# PIC32_Circuit.net
KiCad netlist of a schematic drawn in EAGLE
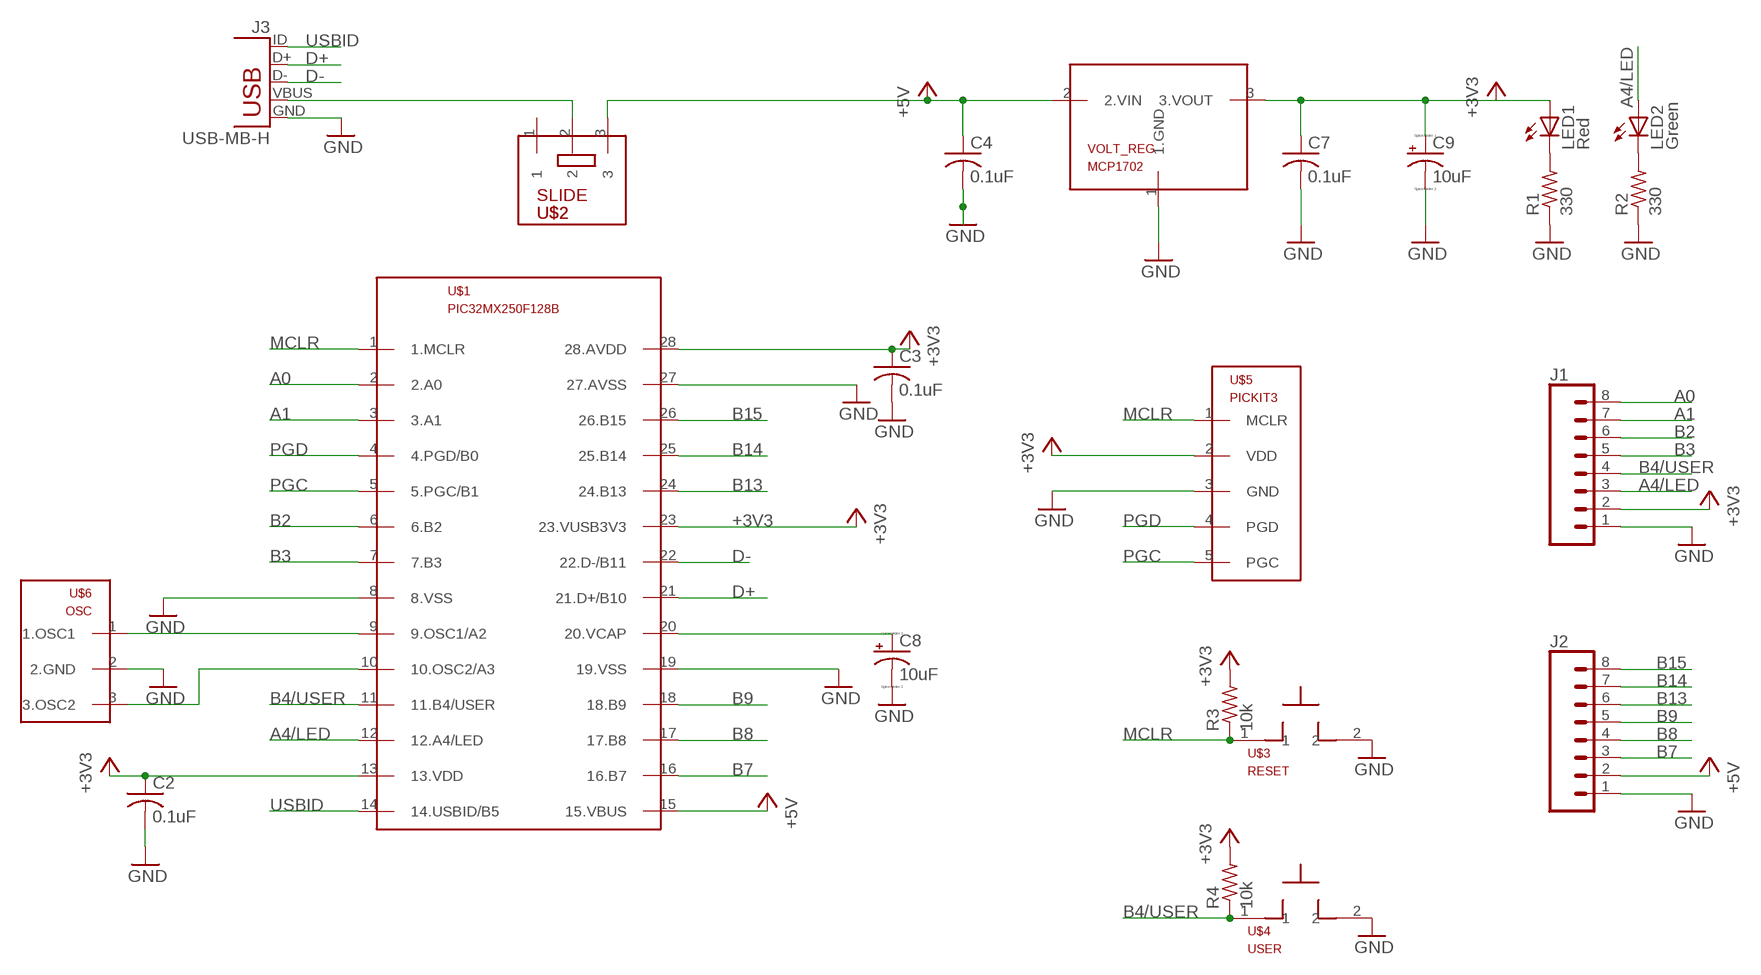
[diagram p0: schematic, sheet 1]

(export (version "E")
  (design (tool "Eeschema 10.0.6"))
  (components
    (comp (ref "C2")
      (value "0.1uF")
      (footprint "eagle-import:C025-050X050")
      (libsource (lib "eagle-import") (part "C-US025-050X050"))
    )
    (comp (ref "C3")
      (value "0.1uF")
      (footprint "eagle-import:C025-050X050")
      (libsource (lib "eagle-import") (part "C-US025-050X050"))
    )
    (comp (ref "C4")
      (value "0.1uF")
      (footprint "eagle-import:C025-050X050")
      (libsource (lib "eagle-import") (part "C-US025-050X050"))
    )
    (comp (ref "C7")
      (value "0.1uF")
      (footprint "eagle-import:C025-050X050")
      (libsource (lib "eagle-import") (part "C-US025-050X050"))
    )
    (comp (ref "C8")
      (value "10uF")
      (footprint "eagle-import:B45181B")
      (libsource (lib "eagle-import") (part "CPOL-USB45181B"))
    )
    (comp (ref "C9")
      (value "10uF")
      (footprint "eagle-import:B45181B")
      (libsource (lib "eagle-import") (part "CPOL-USB45181B"))
    )
    (comp (ref "J1")
      (value "CONN_08\"")
      (footprint "eagle-import:1X08")
      (libsource (lib "eagle-import") (part "CONN_08{dblquote}"))
    )
    (comp (ref "J2")
      (value "CONN_08\"")
      (footprint "eagle-import:1X08")
      (libsource (lib "eagle-import") (part "CONN_08{dblquote}"))
    )
    (comp (ref "J3")
      (value "USB-MB-H")
      (footprint "eagle-import:USB-MB-H")
      (libsource (lib "eagle-import") (part "USB-MB-H"))
    )
    (comp (ref "LED1")
      (value "Red")
      (footprint "eagle-import:LED3MM")
      (libsource (lib "eagle-import") (part "led_LED3MM"))
    )
    (comp (ref "LED2")
      (value "Green")
      (footprint "eagle-import:LED3MM")
      (libsource (lib "eagle-import") (part "LED3MM"))
    )
    (comp (ref "R1")
      (value "330")
      (footprint "eagle-import:0207_10")
      (libsource (lib "eagle-import") (part "R-US_0207/10"))
    )
    (comp (ref "R2")
      (value "330")
      (footprint "eagle-import:0207_10")
      (libsource (lib "eagle-import") (part "R-US_0207/10"))
    )
    (comp (ref "R3")
      (value "10k")
      (footprint "eagle-import:0207_10")
      (libsource (lib "eagle-import") (part "R-US_0207/10"))
    )
    (comp (ref "R4")
      (value "10k")
      (footprint "eagle-import:0207_10")
      (libsource (lib "eagle-import") (part "R-US_0207/10"))
    )
    (comp (ref "U$1")
      (value "PIC32MX250F128B")
      (footprint "eagle-import:DIL28-3")
      (libsource (lib "eagle-import") (part "PIC32MX250F128B"))
    )
    (comp (ref "U$2")
      (value "SLIDE")
      (footprint "eagle-import:SLIDE")
      (libsource (lib "eagle-import") (part "SLIDE"))
    )
    (comp (ref "U$3")
      (value "RESET")
      (footprint "eagle-import:PB")
      (libsource (lib "eagle-import") (part "PB"))
    )
    (comp (ref "U$4")
      (value "USER")
      (footprint "eagle-import:PB")
      (libsource (lib "eagle-import") (part "PB"))
    )
    (comp (ref "U$5")
      (value "PICKIT3")
      (footprint "eagle-import:1X05")
      (libsource (lib "eagle-import") (part "PICKIT3"))
    )
    (comp (ref "U$6")
      (value "OSC")
      (footprint "eagle-import:OSC")
      (libsource (lib "eagle-import") (part "OSC"))
    )
    (comp (ref "VOLT_REG")
      (value "MCP1702")
      (footprint "eagle-import:TO92")
      (libsource (lib "eagle-import") (part "MCP1702"))
    )
  )
  (nets
    (net (code "1") (name "+3V3") (class "Default")
      (node (ref "C2") (pin "1") (pinfunction "1_1") (pintype "passive"))
      (node (ref "C3") (pin "1") (pinfunction "1_1") (pintype "passive"))
      (node (ref "J1") (pin "2") (pinfunction "2_2") (pintype "passive"))
      (node (ref "R3") (pin "2") (pinfunction "2_2") (pintype "passive"))
      (node (ref "R4") (pin "2") (pinfunction "2_2") (pintype "passive"))
      (node (ref "U$1") (pin "13") (pinfunction "13.VDD_13") (pintype "bidirectional"))
      (node (ref "U$1") (pin "23") (pinfunction "23.VUSB3V3_23") (pintype "bidirectional"))
      (node (ref "U$1") (pin "28") (pinfunction "28.AVDD_28") (pintype "bidirectional"))
      (node (ref "U$5") (pin "2") (pinfunction "VDD_2") (pintype "bidirectional"))
    )
    (net (code "2") (name "+5V") (class "Default")
      (node (ref "C4") (pin "1") (pinfunction "1_1") (pintype "passive"))
      (node (ref "J2") (pin "2") (pinfunction "2_2") (pintype "passive"))
      (node (ref "U$1") (pin "15") (pinfunction "15.VBUS_15") (pintype "bidirectional"))
      (node (ref "U$2") (pin "3") (pinfunction "3_3") (pintype "bidirectional"))
      (node (ref "VOLT_REG") (pin "2") (pinfunction "2.VIN_2") (pintype "bidirectional"))
    )
    (net (code "3") (name "/A0") (class "Default")
      (node (ref "J1") (pin "8") (pinfunction "8_8") (pintype "passive"))
      (node (ref "U$1") (pin "2") (pinfunction "2.A0_2") (pintype "bidirectional"))
    )
    (net (code "4") (name "/A1") (class "Default")
      (node (ref "J1") (pin "7") (pinfunction "7_7") (pintype "passive"))
      (node (ref "U$1") (pin "3") (pinfunction "3.A1_3") (pintype "bidirectional"))
    )
    (net (code "5") (name "/A4{slash}LED") (class "Default")
      (node (ref "J1") (pin "3") (pinfunction "3_3") (pintype "passive"))
      (node (ref "LED2") (pin "A") (pinfunction "A_A") (pintype "passive"))
      (node (ref "U$1") (pin "12") (pinfunction "12.A4/LED_12") (pintype "bidirectional"))
    )
    (net (code "6") (name "/B2") (class "Default")
      (node (ref "J1") (pin "6") (pinfunction "6_6") (pintype "passive"))
      (node (ref "U$1") (pin "6") (pinfunction "6.B2_6") (pintype "bidirectional"))
    )
    (net (code "7") (name "/B3") (class "Default")
      (node (ref "J1") (pin "5") (pinfunction "5_5") (pintype "passive"))
      (node (ref "U$1") (pin "7") (pinfunction "7.B3_7") (pintype "bidirectional"))
    )
    (net (code "8") (name "/B4{slash}USER") (class "Default")
      (node (ref "J1") (pin "4") (pinfunction "4_4") (pintype "passive"))
      (node (ref "R4") (pin "1") (pinfunction "1_1") (pintype "passive"))
      (node (ref "U$1") (pin "11") (pinfunction "11.B4/USER_11") (pintype "bidirectional"))
      (node (ref "U$4") (pin "1") (pinfunction "1_1") (pintype "bidirectional"))
    )
    (net (code "9") (name "/B7") (class "Default")
      (node (ref "J2") (pin "3") (pinfunction "3_3") (pintype "passive"))
      (node (ref "U$1") (pin "16") (pinfunction "16.B7_16") (pintype "bidirectional"))
    )
    (net (code "10") (name "/B8") (class "Default")
      (node (ref "J2") (pin "4") (pinfunction "4_4") (pintype "passive"))
      (node (ref "U$1") (pin "17") (pinfunction "17.B8_17") (pintype "bidirectional"))
    )
    (net (code "11") (name "/B9") (class "Default")
      (node (ref "J2") (pin "5") (pinfunction "5_5") (pintype "passive"))
      (node (ref "U$1") (pin "18") (pinfunction "18.B9_18") (pintype "bidirectional"))
    )
    (net (code "12") (name "/B13") (class "Default")
      (node (ref "J2") (pin "6") (pinfunction "6_6") (pintype "passive"))
      (node (ref "U$1") (pin "24") (pinfunction "24.B13_24") (pintype "bidirectional"))
    )
    (net (code "13") (name "/B14") (class "Default")
      (node (ref "J2") (pin "7") (pinfunction "7_7") (pintype "passive"))
      (node (ref "U$1") (pin "25") (pinfunction "25.B14_25") (pintype "bidirectional"))
    )
    (net (code "14") (name "/B15") (class "Default")
      (node (ref "J2") (pin "8") (pinfunction "8_8") (pintype "passive"))
      (node (ref "U$1") (pin "26") (pinfunction "26.B15_26") (pintype "bidirectional"))
    )
    (net (code "15") (name "/D+") (class "Default")
      (node (ref "J3") (pin "D+") (pinfunction "D+_D+") (pintype "bidirectional"))
      (node (ref "U$1") (pin "21") (pinfunction "21.D+/B10_21") (pintype "bidirectional"))
    )
    (net (code "16") (name "/D-") (class "Default")
      (node (ref "J3") (pin "D-") (pinfunction "D-_D-") (pintype "bidirectional"))
      (node (ref "U$1") (pin "22") (pinfunction "22.D-/B11_22") (pintype "bidirectional"))
    )
    (net (code "17") (name "/MCLR") (class "Default")
      (node (ref "R3") (pin "1") (pinfunction "1_1") (pintype "passive"))
      (node (ref "U$1") (pin "1") (pinfunction "1.MCLR_1") (pintype "bidirectional"))
      (node (ref "U$3") (pin "1") (pinfunction "1_1") (pintype "bidirectional"))
      (node (ref "U$5") (pin "1") (pinfunction "MCLR_1") (pintype "bidirectional"))
    )
    (net (code "18") (name "/PGC") (class "Default")
      (node (ref "U$1") (pin "5") (pinfunction "5.PGC/B1_5") (pintype "bidirectional"))
      (node (ref "U$5") (pin "5") (pinfunction "PGC_5") (pintype "bidirectional"))
    )
    (net (code "19") (name "/PGD") (class "Default")
      (node (ref "U$1") (pin "4") (pinfunction "4.PGD/B0_4") (pintype "bidirectional"))
      (node (ref "U$5") (pin "4") (pinfunction "PGD_4") (pintype "bidirectional"))
    )
    (net (code "20") (name "/USBID") (class "Default")
      (node (ref "J3") (pin "ID") (pinfunction "ID_ID") (pintype "bidirectional"))
      (node (ref "U$1") (pin "14") (pinfunction "14.USBID/B5_14") (pintype "bidirectional"))
    )
    (net (code "21") (name "GND") (class "Default")
      (node (ref "C2") (pin "2") (pinfunction "2_2") (pintype "passive"))
      (node (ref "C3") (pin "2") (pinfunction "2_2") (pintype "passive"))
      (node (ref "C4") (pin "2") (pinfunction "2_2") (pintype "passive"))
      (node (ref "C7") (pin "2") (pinfunction "2_2") (pintype "passive"))
      (node (ref "C8") (pin "-") (pinfunction "-_-") (pintype "passive"))
      (node (ref "C9") (pin "-") (pinfunction "-_-") (pintype "passive"))
      (node (ref "J1") (pin "1") (pinfunction "1_1") (pintype "passive"))
      (node (ref "J2") (pin "1") (pinfunction "1_1") (pintype "passive"))
      (node (ref "J3") (pin "GND") (pinfunction "GND_GND") (pintype "bidirectional"))
      (node (ref "R1") (pin "1") (pinfunction "1_1") (pintype "passive"))
      (node (ref "R2") (pin "1") (pinfunction "1_1") (pintype "passive"))
      (node (ref "U$1") (pin "19") (pinfunction "19.VSS_19") (pintype "bidirectional"))
      (node (ref "U$1") (pin "27") (pinfunction "27.AVSS_27") (pintype "bidirectional"))
      (node (ref "U$1") (pin "8") (pinfunction "8.VSS_8") (pintype "bidirectional"))
      (node (ref "U$3") (pin "2") (pinfunction "2_2") (pintype "bidirectional"))
      (node (ref "U$4") (pin "2") (pinfunction "2_2") (pintype "bidirectional"))
      (node (ref "U$5") (pin "3") (pinfunction "GND_3") (pintype "bidirectional"))
      (node (ref "U$6") (pin "2") (pinfunction "2.GND_2") (pintype "bidirectional"))
      (node (ref "VOLT_REG") (pin "1") (pinfunction "1.GND_1") (pintype "bidirectional"))
    )
    (net (code "22") (name "Net-(J3-PadVBUS)") (class "Default")
      (node (ref "J3") (pin "VBUS") (pinfunction "VBUS_VBUS") (pintype "bidirectional"))
      (node (ref "U$2") (pin "2") (pinfunction "2_2") (pintype "bidirectional"))
    )
    (net (code "23") (name "Net-(LED1-C)") (class "Default")
      (node (ref "LED1") (pin "K") (pinfunction "C_K") (pintype "passive"))
      (node (ref "R1") (pin "2") (pinfunction "2_2") (pintype "passive"))
    )
    (net (code "24") (name "Net-(LED2-C)") (class "Default")
      (node (ref "LED2") (pin "K") (pinfunction "C_K") (pintype "passive"))
      (node (ref "R2") (pin "2") (pinfunction "2_2") (pintype "passive"))
    )
    (net (code "25") (name "Net-(U$1-9.OSC1{slash}A2)") (class "Default")
      (node (ref "U$1") (pin "9") (pinfunction "9.OSC1/A2_9") (pintype "bidirectional"))
      (node (ref "U$6") (pin "1") (pinfunction "1.OSC1_1") (pintype "bidirectional"))
    )
    (net (code "26") (name "Net-(U$1-10.OSC2{slash}A3)") (class "Default")
      (node (ref "U$1") (pin "10") (pinfunction "10.OSC2/A3_10") (pintype "bidirectional"))
      (node (ref "U$6") (pin "3") (pinfunction "3.OSC2_3") (pintype "bidirectional"))
    )
    (net (code "27") (name "Net-(U$1-20.VCAP)") (class "Default")
      (node (ref "C8") (pin "+") (pinfunction "+_+") (pintype "passive"))
      (node (ref "U$1") (pin "20") (pinfunction "20.VCAP_20") (pintype "bidirectional"))
    )
    (net (code "28") (name "Net-(VOLT_REG-3.VOUT)") (class "Default")
      (node (ref "C7") (pin "1") (pinfunction "1_1") (pintype "passive"))
      (node (ref "C9") (pin "+") (pinfunction "+_+") (pintype "passive"))
      (node (ref "LED1") (pin "A") (pinfunction "A_A") (pintype "passive"))
      (node (ref "VOLT_REG") (pin "3") (pinfunction "3.VOUT_3") (pintype "bidirectional"))
    )
    (net (code "29") (name "unconnected-(U$2-Pad1)") (class "Default")
      (node (ref "U$2") (pin "1") (pinfunction "1_1") (pintype "bidirectional"))
    )
  )
)
